# AdelinoR1.net
KiCad netlist of a schematic drawn in EAGLE
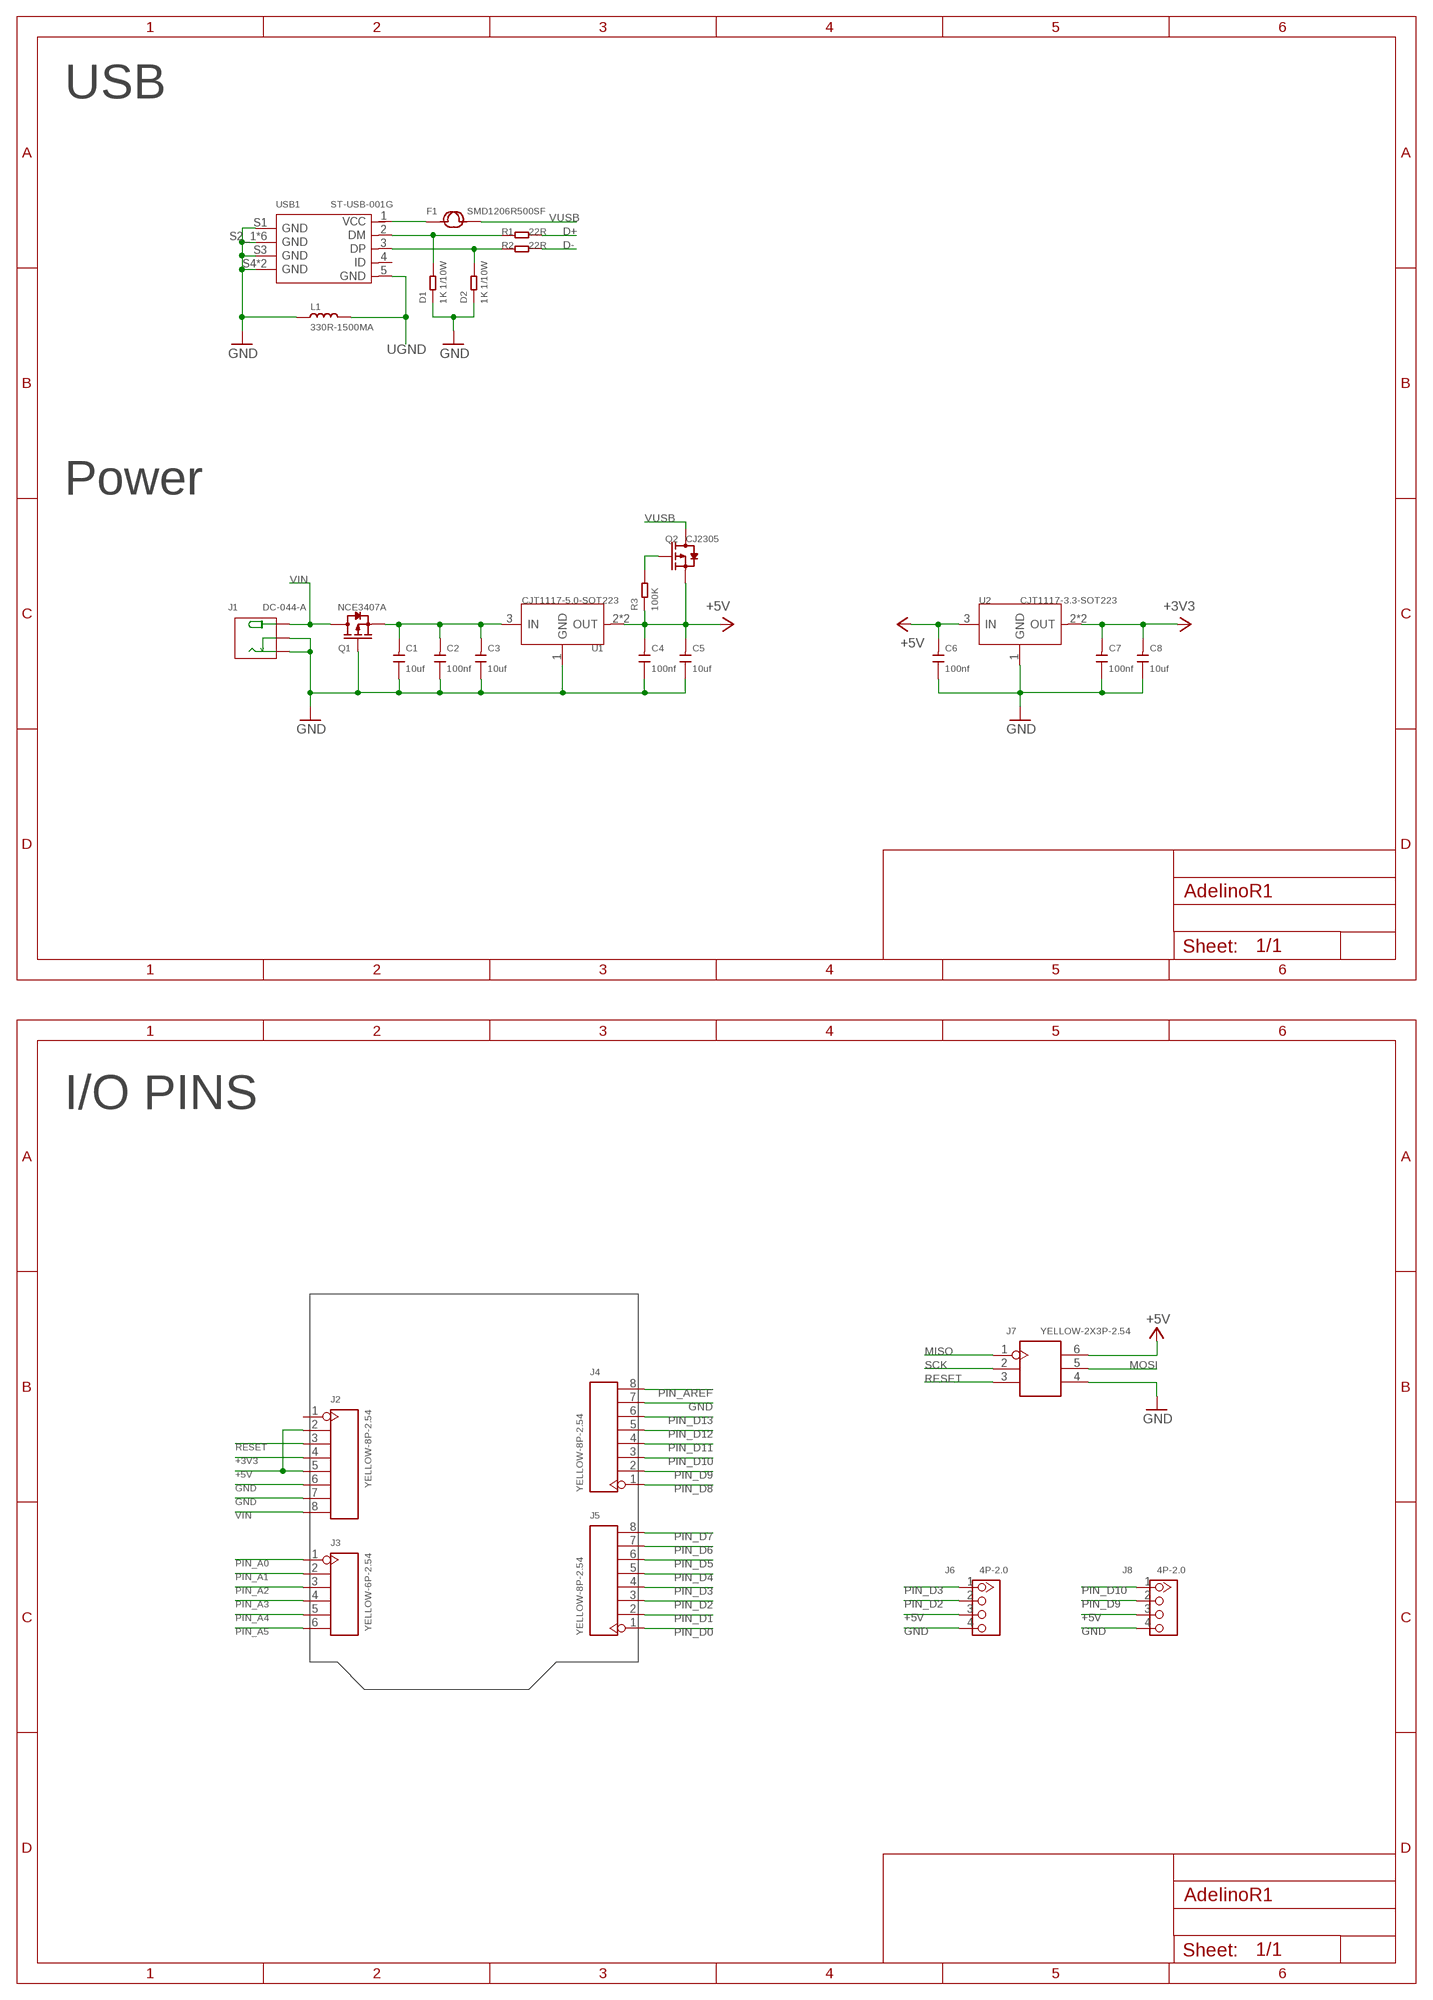
[diagram p0: schematic, sheet 1, part 1 of 2]
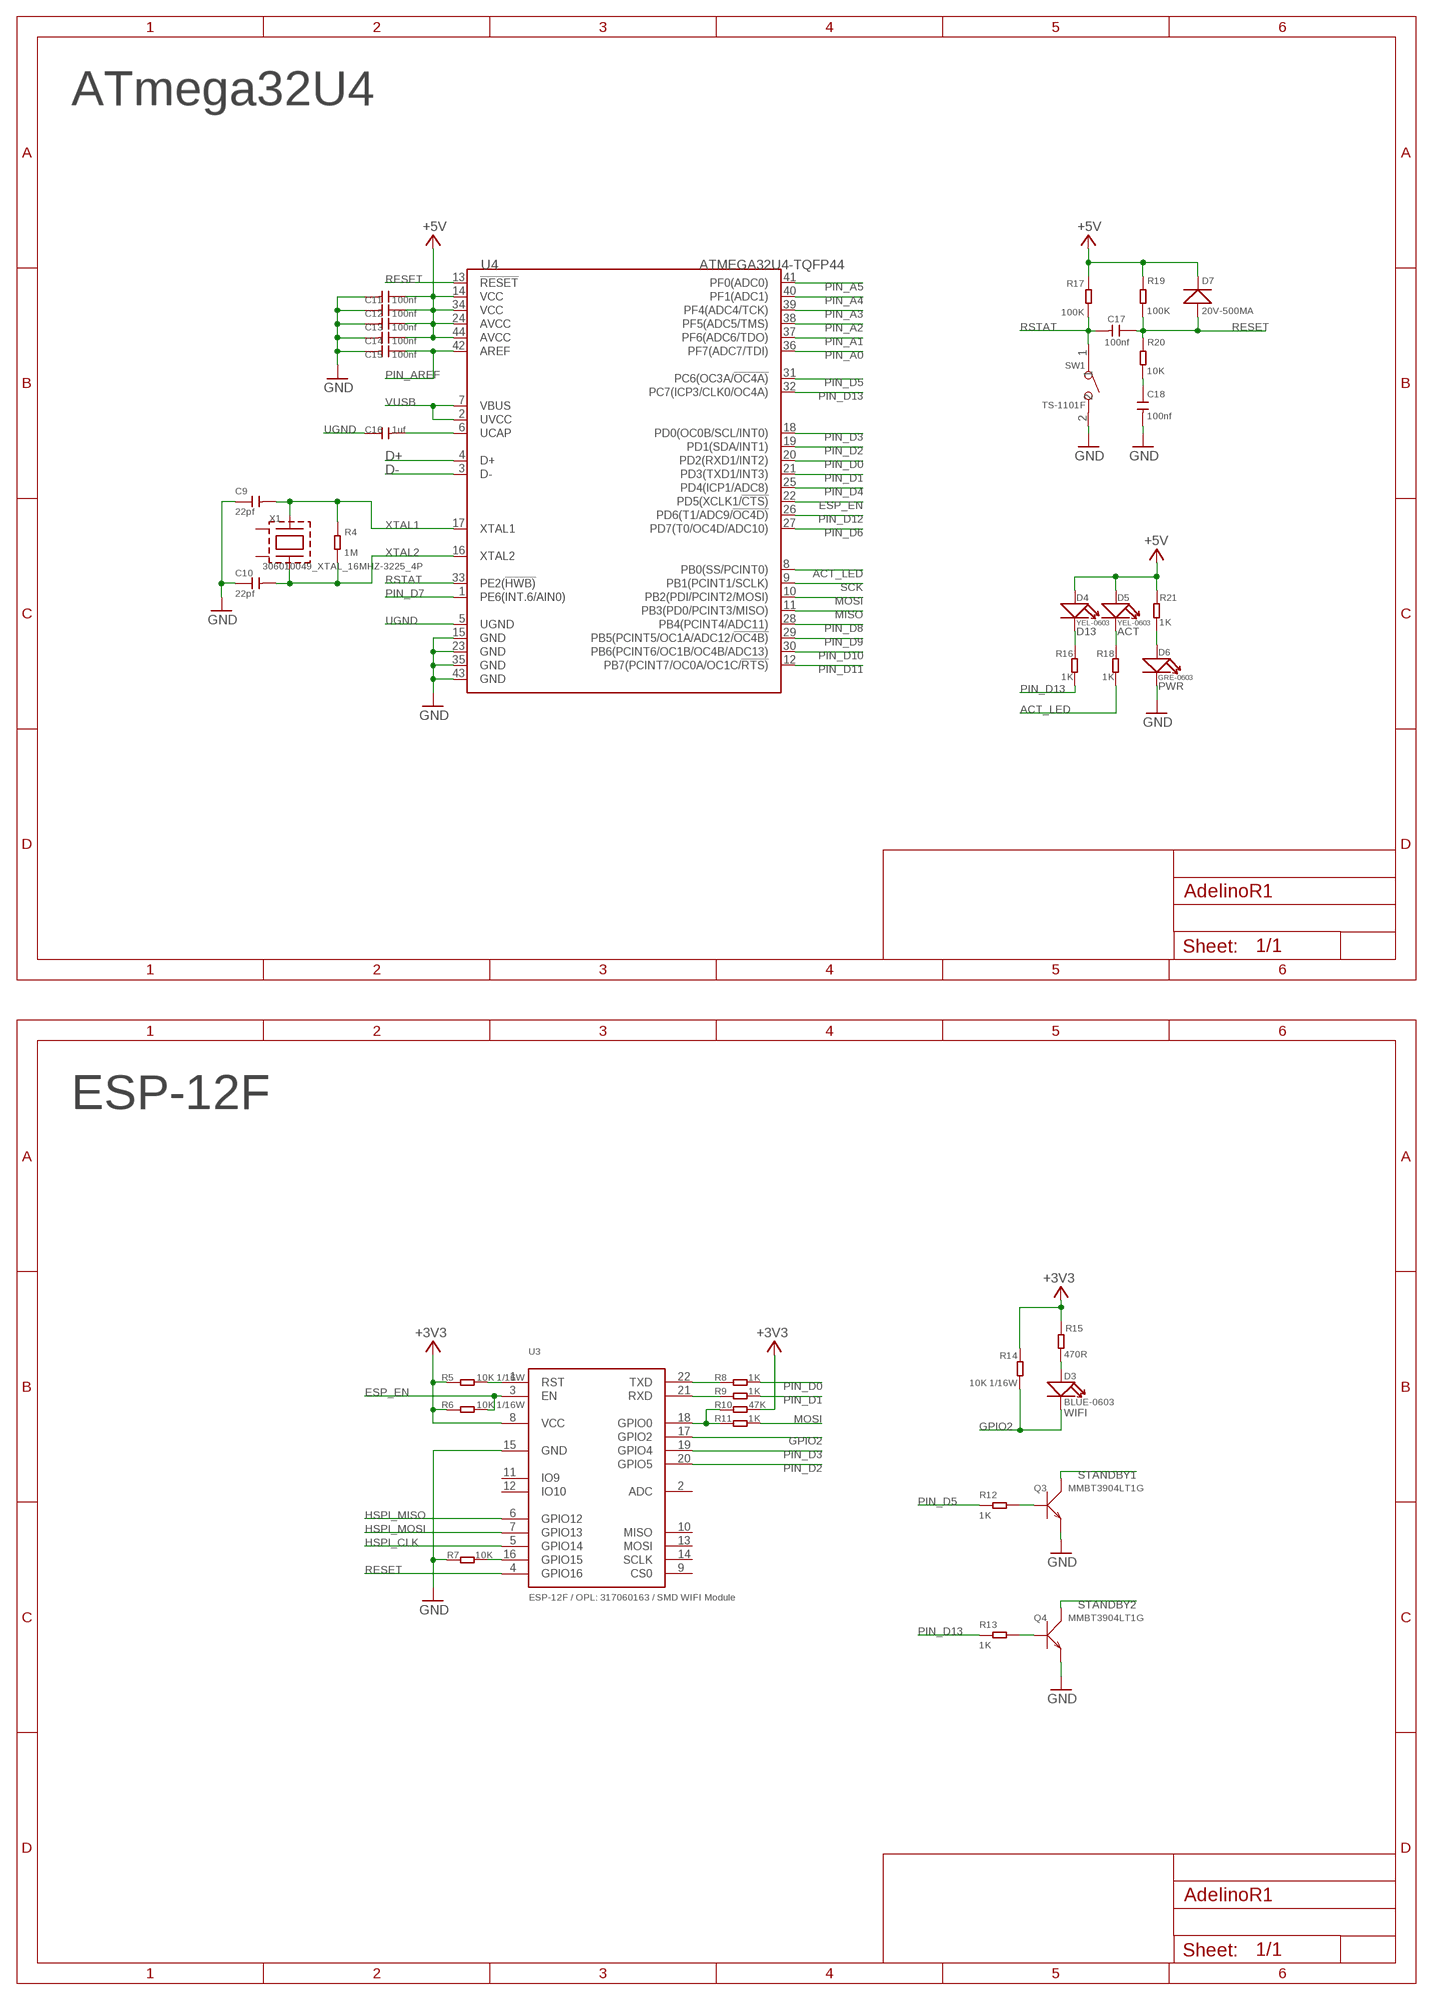
[diagram p1: schematic, sheet 1, part 2 of 2]

(export (version "E")
  (design (tool "Eeschema 10.0.6"))
  (components
    (comp (ref "C1")
      (value "10uf")
      (footprint "eagle-import:C0805")
      (fields (field (name "MPN") "CC0805KKX5R8BB106"))
      (libsource (lib "eagle-import") (part "CERAMIC-10UF-25V-10%-X5R(0805)"))
    )
    (comp (ref "C2")
      (value "100nf")
      (footprint "eagle-import:C0402")
      (fields (field (name "MPN") "CC0402KRX7R8BB104"))
      (libsource (lib "eagle-import") (part "CERAMIC-100NF-25V-10%-X7R(0402)"))
    )
    (comp (ref "C3")
      (value "10uf")
      (footprint "eagle-import:C0805")
      (fields (field (name "MPN") "CC0805KKX5R8BB106"))
      (libsource (lib "eagle-import") (part "CERAMIC-10UF-25V-10%-X5R(0805)"))
    )
    (comp (ref "C4")
      (value "100nf")
      (footprint "eagle-import:C0402")
      (fields (field (name "MPN") "CC0402KRX7R8BB104"))
      (libsource (lib "eagle-import") (part "CERAMIC-100NF-25V-10%-X7R(0402)"))
    )
    (comp (ref "C5")
      (value "10uf")
      (footprint "eagle-import:C0805")
      (fields (field (name "MPN") "CC0805KKX5R8BB106"))
      (libsource (lib "eagle-import") (part "CERAMIC-10UF-25V-10%-X5R(0805)"))
    )
    (comp (ref "C6")
      (value "100nf")
      (footprint "eagle-import:C0402")
      (fields (field (name "MPN") "CC0402KRX7R8BB104"))
      (libsource (lib "eagle-import") (part "CERAMIC-100NF-25V-10%-X7R(0402)"))
    )
    (comp (ref "C7")
      (value "100nf")
      (footprint "eagle-import:C0402")
      (fields (field (name "MPN") "CC0402KRX7R8BB104"))
      (libsource (lib "eagle-import") (part "CERAMIC-100NF-25V-10%-X7R(0402)"))
    )
    (comp (ref "C8")
      (value "10uf")
      (footprint "eagle-import:C0805")
      (fields (field (name "MPN") "CC0805KKX5R8BB106"))
      (libsource (lib "eagle-import") (part "CERAMIC-10UF-25V-10%-X5R(0805)"))
    )
    (comp (ref "C9")
      (value "22pf")
      (footprint "eagle-import:C0402")
      (fields (field (name "MPN") "CC0402JRNPO9BN220"))
      (libsource (lib "eagle-import") (part "CERAMIC-22PF-50V-5%-NPO(0402)"))
    )
    (comp (ref "C10")
      (value "22pf")
      (footprint "eagle-import:C0402")
      (fields (field (name "MPN") "CC0402JRNPO9BN220"))
      (libsource (lib "eagle-import") (part "CERAMIC-22PF-50V-5%-NPO(0402)"))
    )
    (comp (ref "C11")
      (value "100nf")
      (footprint "eagle-import:C0402")
      (fields (field (name "MPN") "CC0402KRX7R8BB104"))
      (libsource (lib "eagle-import") (part "CERAMIC-100NF-25V-10%-X7R(0402)"))
    )
    (comp (ref "C12")
      (value "100nf")
      (footprint "eagle-import:C0402")
      (fields (field (name "MPN") "CC0402KRX7R8BB104"))
      (libsource (lib "eagle-import") (part "CERAMIC-100NF-25V-10%-X7R(0402)"))
    )
    (comp (ref "C13")
      (value "100nf")
      (footprint "eagle-import:C0402")
      (fields (field (name "MPN") "CC0402KRX7R8BB104"))
      (libsource (lib "eagle-import") (part "CERAMIC-100NF-25V-10%-X7R(0402)"))
    )
    (comp (ref "C14")
      (value "100nf")
      (footprint "eagle-import:C0402")
      (fields (field (name "MPN") "CC0402KRX7R8BB104"))
      (libsource (lib "eagle-import") (part "CERAMIC-100NF-25V-10%-X7R(0402)"))
    )
    (comp (ref "C15")
      (value "100nf")
      (footprint "eagle-import:C0402")
      (fields (field (name "MPN") "CC0402KRX7R8BB104"))
      (libsource (lib "eagle-import") (part "CERAMIC-100NF-25V-10%-X7R(0402)"))
    )
    (comp (ref "C16")
      (value "1uf")
      (footprint "eagle-import:C0805")
      (fields (field (name "MPN") "CC0805KKX7R8BB105"))
      (libsource (lib "eagle-import") (part "CERAMIC-1UF-25V-10%-X7R(0805)"))
    )
    (comp (ref "C17")
      (value "100nf")
      (footprint "eagle-import:C0402")
      (fields (field (name "MPN") "CC0402KRX7R8BB104"))
      (libsource (lib "eagle-import") (part "CERAMIC-100NF-25V-10%-X7R(0402)"))
    )
    (comp (ref "C18")
      (value "100nf")
      (footprint "eagle-import:C0402")
      (fields (field (name "MPN") "CC0402KRX7R8BB104"))
      (libsource (lib "eagle-import") (part "CERAMIC-100NF-25V-10%-X7R(0402)"))
    )
    (comp (ref "D1")
      (value "1K 1/10W")
      (footprint "eagle-import:D0603")
      (fields (field (name "MPN") "RC0603JR-071KL"))
      (libsource (lib "eagle-import") (part "SMD-ESD-CG0603MLC-05E"))
    )
    (comp (ref "D2")
      (value "1K 1/10W")
      (footprint "eagle-import:D0603")
      (fields (field (name "MPN") "RC0603JR-071KL"))
      (libsource (lib "eagle-import") (part "SMD-ESD-CG0603MLC-05E"))
    )
    (comp (ref "D3")
      (value "BLUE-0603")
      (footprint "eagle-import:LED-0603")
      (fields (field (name "MPN") "19-217-BHC-ZL1M2RY-3T") (field (name "LABEL") "WIFI"))
      (libsource (lib "eagle-import") (part "SMD-LED-CLEAR-BLUE(0603)"))
    )
    (comp (ref "D4")
      (value "YEL-0603")
      (footprint "eagle-import:LED-0603")
      (fields (field (name "MPN") "19-217-Y5C-AM1N1VY-3T") (field (name "LABEL") "D13"))
      (libsource (lib "eagle-import") (part "SMD-LED-CLEAR-YELLOW(0603)"))
    )
    (comp (ref "D5")
      (value "YEL-0603")
      (footprint "eagle-import:LED-0603")
      (fields (field (name "MPN") "19-217-Y5C-AM1N1VY-3T") (field (name "LABEL") "ACT"))
      (libsource (lib "eagle-import") (part "SMD-LED-CLEAR-YELLOW(0603)"))
    )
    (comp (ref "D6")
      (value "GRE-0603")
      (footprint "eagle-import:LED-0603")
      (fields (field (name "MPN") "19-217-G7C-AN1P2-3T") (field (name "LABEL") "PWR"))
      (libsource (lib "eagle-import") (part "SMD-LED-CLEAR-GREEN(0603)"))
    )
    (comp (ref "D7")
      (value "20V-500MA")
      (footprint "eagle-import:SOD-123")
      (fields (field (name "MPN") "MBR0520LT1G"))
      (libsource (lib "eagle-import") (part "SMD-DIODE-SCHOTTKY-20V-500MA(SOD-123)P"))
    )
    (comp (ref "F1")
      (value "SMD1206R500SF")
      (footprint "eagle-import:F1206")
      (libsource (lib "eagle-import") (part "SMD-PPTC-500MA(1206)"))
    )
    (comp (ref "J1")
      (value "DC-044-A")
      (footprint "eagle-import:DCJ3P-11.6X9.6X7.0MM")
      (fields (field (name "MPN") "JACK-DC-044-A"))
      (libsource (lib "eagle-import") (part "JACK-DC-044-A"))
    )
    (comp (ref "J2")
      (value "YELLOW-8P-2.54")
      (footprint "eagle-import:H8-2.54")
      (fields (field (name "MPN") "F185-1108A1BSYC1"))
      (libsource (lib "eagle-import") (part "DIP-YELLOW-FEMALE-HEADER(8P-2.54)"))
    )
    (comp (ref "J3")
      (value "YELLOW-6P-2.54")
      (footprint "eagle-import:H6-2.54")
      (fields (field (name "MPN") "F185-1106A1BSYA3"))
      (libsource (lib "eagle-import") (part "DIP-YELLOW-FEMALE-HEADER-VERT(6P-2.54)"))
    )
    (comp (ref "J4")
      (value "YELLOW-8P-2.54")
      (footprint "eagle-import:H8-2.54")
      (fields (field (name "MPN") "F185-1108A1BSYC1"))
      (libsource (lib "eagle-import") (part "DIP-YELLOW-FEMALE-HEADER(8P-2.54)"))
    )
    (comp (ref "J5")
      (value "YELLOW-8P-2.54")
      (footprint "eagle-import:H8-2.54")
      (fields (field (name "MPN") "F185-1108A1BSYC1"))
      (libsource (lib "eagle-import") (part "DIP-YELLOW-FEMALE-HEADER(8P-2.54)"))
    )
    (comp (ref "J6")
      (value "4P-2.0")
      (footprint "eagle-import:HW4-2.0")
      (libsource (lib "eagle-import") (part "GROVE-CONNECTOR-DIP(4P-2.0)"))
    )
    (comp (ref "J7")
      (value "YELLOW-2X3P-2.54")
      (footprint "eagle-import:H2X3-2.54")
      (fields (field (name "MPN") "P125-1203A0BS116A2"))
      (libsource (lib "eagle-import") (part "DIP-YELLOW-MALE-HEADER-VERT(2X3P-2.54)"))
    )
    (comp (ref "J8")
      (value "4P-2.0")
      (footprint "eagle-import:HW4-2.0")
      (libsource (lib "eagle-import") (part "GROVE-CONNECTOR-DIP(4P-2.0)"))
    )
    (comp (ref "L1")
      (value "330R-1500MA")
      (footprint "eagle-import:L0805")
      (fields (field (name "MPN") "BLM21PG331SN1D"))
      (libsource (lib "eagle-import") (part "SMD-FERRITE-BEAD-330R-1500MA(0805)'0805'"))
    )
    (comp (ref "Q1")
      (value "NCE3407A")
      (footprint "eagle-import:SOT-23")
      (libsource (lib "eagle-import") (part "SMD-MOSFET-P-CH-VDC=30V-ID=4.3A-NCE3407A(SOT-23)"))
    )
    (comp (ref "Q2")
      (value "CJ2305")
      (footprint "eagle-import:SOT-23")
      (libsource (lib "eagle-import") (part "SMD-MOSFET-P-CH-8V-4.1A-CJ2305(SOT-23)"))
    )
    (comp (ref "Q3")
      (value "MMBT3904LT1G")
      (footprint "eagle-import:SOT-23")
      (libsource (lib "eagle-import") (part "SMD-TRANSISTORS-NPN-40V-200MA-MMBT3904LT1G(SOT-23)"))
    )
    (comp (ref "Q4")
      (value "MMBT3904LT1G")
      (footprint "eagle-import:SOT-23")
      (libsource (lib "eagle-import") (part "SMD-TRANSISTORS-NPN-40V-200MA-MMBT3904LT1G(SOT-23)"))
    )
    (comp (ref "R1")
      (value "22R")
      (footprint "eagle-import:R0402")
      (fields (field (name "MPN") "RC0402FR-0722RL"))
      (libsource (lib "eagle-import") (part "SMD-RES-22R-1%-1/16W(0402)"))
    )
    (comp (ref "R2")
      (value "22R")
      (footprint "eagle-import:R0402")
      (fields (field (name "MPN") "RC0402FR-0722RL"))
      (libsource (lib "eagle-import") (part "SMD-RES-22R-1%-1/16W(0402)"))
    )
    (comp (ref "R3")
      (value "100K")
      (footprint "eagle-import:R0402")
      (fields (field (name "MPN") "RC0402FR-07100KL"))
      (libsource (lib "eagle-import") (part "SMD-RES-100K-1%-1/16W(0402)"))
    )
    (comp (ref "R4")
      (value "1M")
      (footprint "eagle-import:R0402")
      (fields (field (name "MPN") "RC0402FR-071ML"))
      (libsource (lib "eagle-import") (part "SMD-RES-1M-1%-1/16W(0402)"))
    )
    (comp (ref "R5")
      (value "10K 1/16W")
      (footprint "eagle-import:R0402")
      (fields (field (name "MPN") "RC0402FR-0710KL"))
      (libsource (lib "eagle-import") (part "SMD-RES-10K-1%-1/16W(0402)"))
    )
    (comp (ref "R6")
      (value "10K 1/16W")
      (footprint "eagle-import:R0402")
      (fields (field (name "MPN") "RC0402FR-0710KL"))
      (libsource (lib "eagle-import") (part "SMD-RES-10K-1%-1/16W(0402)"))
    )
    (comp (ref "R7")
      (value "10K")
      (footprint "eagle-import:R0402")
      (fields (field (name "MPN") "RC0402FR-0710KL"))
      (libsource (lib "eagle-import") (part "SMD-RES-10K-1%-1/16W(0402)"))
    )
    (comp (ref "R8")
      (value "1K")
      (footprint "eagle-import:R0402")
      (fields (field (name "MPN") "RC0402JR-071KL"))
      (libsource (lib "eagle-import") (part "SMD-RES-1K-5%-1/16W(0402)"))
    )
    (comp (ref "R9")
      (value "1K")
      (footprint "eagle-import:R0402")
      (fields (field (name "MPN") "RC0402JR-071KL"))
      (libsource (lib "eagle-import") (part "SMD-RES-1K-5%-1/16W(0402)"))
    )
    (comp (ref "R10")
      (value "47K")
      (footprint "eagle-import:R0402")
      (fields (field (name "MPN") "RC0402JR-0747KL"))
      (libsource (lib "eagle-import") (part "SMD-RES-47K-5%-1/16W(0402)"))
    )
    (comp (ref "R11")
      (value "1K")
      (footprint "eagle-import:R0402")
      (fields (field (name "MPN") "RC0402JR-071KL"))
      (libsource (lib "eagle-import") (part "SMD-RES-1K-5%-1/16W(0402)"))
    )
    (comp (ref "R12")
      (value "1K")
      (footprint "eagle-import:R0402")
      (fields (field (name "MPN") "RC0402JR-071KL"))
      (libsource (lib "eagle-import") (part "SMD-RES-1K-5%-1/16W(0402)"))
    )
    (comp (ref "R13")
      (value "1K")
      (footprint "eagle-import:R0402")
      (fields (field (name "MPN") "RC0402JR-071KL"))
      (libsource (lib "eagle-import") (part "SMD-RES-1K-5%-1/16W(0402)"))
    )
    (comp (ref "R14")
      (value "10K 1/16W")
      (footprint "eagle-import:R0402")
      (fields (field (name "MPN") "RC0402FR-0710KL"))
      (libsource (lib "eagle-import") (part "SMD-RES-10K-1%-1/16W(0402)"))
    )
    (comp (ref "R15")
      (value "470R")
      (footprint "eagle-import:R0402")
      (fields (field (name "MPN") "RC0402JR-07470RL"))
      (libsource (lib "eagle-import") (part "SMD-RES-470R-5%-1/16W(0402)"))
    )
    (comp (ref "R16")
      (value "1K")
      (footprint "eagle-import:R0402")
      (fields (field (name "MPN") "RC0402JR-071KL"))
      (libsource (lib "eagle-import") (part "SMD-RES-1K-5%-1/16W(0402)"))
    )
    (comp (ref "R17")
      (value "100K")
      (footprint "eagle-import:R0402")
      (fields (field (name "MPN") "RC0402FR-07100KL"))
      (libsource (lib "eagle-import") (part "SMD-RES-100K-1%-1/16W(0402)"))
    )
    (comp (ref "R18")
      (value "1K")
      (footprint "eagle-import:R0402")
      (fields (field (name "MPN") "RC0402JR-071KL"))
      (libsource (lib "eagle-import") (part "SMD-RES-1K-5%-1/16W(0402)"))
    )
    (comp (ref "R19")
      (value "100K")
      (footprint "eagle-import:R0402")
      (fields (field (name "MPN") "RC0402FR-07100KL"))
      (libsource (lib "eagle-import") (part "SMD-RES-100K-1%-1/16W(0402)"))
    )
    (comp (ref "R20")
      (value "10K")
      (footprint "eagle-import:R0402")
      (fields (field (name "MPN") "RC0402FR-0710KL"))
      (libsource (lib "eagle-import") (part "SMD-RES-10K-1%-1/16W(0402)"))
    )
    (comp (ref "R21")
      (value "1K")
      (footprint "eagle-import:R0402")
      (fields (field (name "MPN") "RC0402JR-071KL"))
      (libsource (lib "eagle-import") (part "SMD-RES-1K-5%-1/16W(0402)"))
    )
    (comp (ref "SW1")
      (value "TS-1101F")
      (footprint "eagle-import:SW2-5.0-6.0X3.0X4.3MM")
      (libsource (lib "eagle-import") (part "DIP-BUTTON(2P-6.0X3.0X4.3MM)-TS-1101F"))
    )
    (comp (ref "U1")
      (value "CJT1117-5.0-SOT223")
      (footprint "eagle-import:SOT-223")
      (fields (field (name "MPN") "CJT1117-5.0"))
      (libsource (lib "eagle-import") (part "PMIC-CJT1117-5.0(SOT223)"))
    )
    (comp (ref "U2")
      (value "CJT1117-3.3-SOT223")
      (footprint "eagle-import:SOT-223")
      (fields (field (name "MPN") "CJT1117-3.3"))
      (libsource (lib "eagle-import") (part "PMIC-CJT1117-3.3(SOT223)"))
    )
    (comp (ref "U3")
      (value "ESP-12F / OPL: 317060163 / SMD WIFI Module")
      (footprint "eagle-import:ESP-12F")
      (libsource (lib "eagle-import") (part "ESP-12F"))
    )
    (comp (ref "U4")
      (value "ATMEGA32U4-TQFP44")
      (footprint "eagle-import:TQFP44-0.8-9.6X9.6MM")
      (fields (field (name "MPN") "ATMEGA32U4"))
      (libsource (lib "eagle-import") (part "MCU-ATMEGA32U4-AU(TQFP44)"))
    )
    (comp (ref "USB1")
      (value "ST-USB-001G")
      (footprint "eagle-import:MICRO-USB5+4P-SMD-0.65-B")
      (libsource (lib "eagle-import") (part "MICRO-USB-SMD-B-WITHOUT-POST-W/P(ST-USB-001G)"))
    )
    (comp (ref "X1")
      (value "306010049_XTAL_16MHZ-3225_4P")
      (footprint "eagle-import:X3225_4P")
      (libsource (lib "eagle-import") (part "306010049_XTAL_16MHZ-3225_4P"))
    )
  )
  (nets
    (net (code "1") (name "+3V3") (class "Default")
      (node (ref "C7") (pin "2") (pinfunction "2_2") (pintype "passive"))
      (node (ref "C8") (pin "2") (pinfunction "2_2") (pintype "passive"))
      (node (ref "J2") (pin "4") (pinfunction "4_4") (pintype "bidirectional"))
      (node (ref "R10") (pin "2") (pinfunction "2_2") (pintype "passive"))
      (node (ref "R14") (pin "2") (pinfunction "2_2") (pintype "passive"))
      (node (ref "R15") (pin "2") (pinfunction "2_2") (pintype "passive"))
      (node (ref "R5") (pin "1") (pinfunction "1_1") (pintype "passive"))
      (node (ref "R6") (pin "1") (pinfunction "1_1") (pintype "passive"))
      (node (ref "U2") (pin "2") (pinfunction "OUT_2") (pintype "bidirectional"))
      (node (ref "U2") (pin "TER") (pinfunction "OUT_TER") (pintype "bidirectional"))
      (node (ref "U3") (pin "8") (pinfunction "VCC_8") (pintype "bidirectional"))
    )
    (net (code "2") (name "+5V") (class "Default")
      (node (ref "C11") (pin "1") (pinfunction "1_1") (pintype "passive"))
      (node (ref "C12") (pin "1") (pinfunction "1_1") (pintype "passive"))
      (node (ref "C13") (pin "1") (pinfunction "1_1") (pintype "passive"))
      (node (ref "C14") (pin "1") (pinfunction "1_1") (pintype "passive"))
      (node (ref "C4") (pin "2") (pinfunction "2_2") (pintype "passive"))
      (node (ref "C5") (pin "2") (pinfunction "2_2") (pintype "passive"))
      (node (ref "C6") (pin "2") (pinfunction "2_2") (pintype "passive"))
      (node (ref "D4") (pin "+") (pinfunction "+_+") (pintype "passive"))
      (node (ref "D5") (pin "+") (pinfunction "+_+") (pintype "passive"))
      (node (ref "D7") (pin "-") (pinfunction "-_-") (pintype "passive"))
      (node (ref "J2") (pin "2") (pinfunction "2_2") (pintype "bidirectional"))
      (node (ref "J2") (pin "5") (pinfunction "5_5") (pintype "bidirectional"))
      (node (ref "J6") (pin "3") (pinfunction "3_3") (pintype "bidirectional"))
      (node (ref "J7") (pin "6") (pinfunction "6_6") (pintype "bidirectional"))
      (node (ref "J8") (pin "3") (pinfunction "3_3") (pintype "bidirectional"))
      (node (ref "Q2") (pin "2") (pinfunction "S_2") (pintype "passive"))
      (node (ref "R17") (pin "1") (pinfunction "1_1") (pintype "passive"))
      (node (ref "R19") (pin "2") (pinfunction "2_2") (pintype "passive"))
      (node (ref "R21") (pin "1") (pinfunction "1_1") (pintype "passive"))
      (node (ref "R3") (pin "1") (pinfunction "1_1") (pintype "passive"))
      (node (ref "U1") (pin "2") (pinfunction "OUT_2") (pintype "bidirectional"))
      (node (ref "U1") (pin "TER") (pinfunction "OUT_TER") (pintype "bidirectional"))
      (node (ref "U2") (pin "3") (pinfunction "IN_3") (pintype "bidirectional"))
      (node (ref "U4") (pin "14") (pinfunction "VCC_14") (pintype "bidirectional"))
      (node (ref "U4") (pin "24") (pinfunction "AVCC_24") (pintype "bidirectional"))
      (node (ref "U4") (pin "34") (pinfunction "VCC_34") (pintype "bidirectional"))
      (node (ref "U4") (pin "44") (pinfunction "AVCC_44") (pintype "bidirectional"))
    )
    (net (code "3") (name "/ACT_LED") (class "Default")
      (node (ref "R18") (pin "2") (pinfunction "2_2") (pintype "passive"))
      (node (ref "U4") (pin "8") (pinfunction "PB0(SS/PCINT0)_8") (pintype "bidirectional"))
    )
    (net (code "4") (name "/D+") (class "Default")
      (node (ref "R1") (pin "2") (pinfunction "2_2") (pintype "passive"))
      (node (ref "U4") (pin "4") (pinfunction "D+_4") (pintype "bidirectional"))
    )
    (net (code "5") (name "/D-") (class "Default")
      (node (ref "R2") (pin "2") (pinfunction "2_2") (pintype "passive"))
      (node (ref "U4") (pin "3") (pinfunction "D-_3") (pintype "bidirectional"))
    )
    (net (code "6") (name "/ESP_EN") (class "Default")
      (node (ref "R6") (pin "2") (pinfunction "2_2") (pintype "passive"))
      (node (ref "U3") (pin "3") (pinfunction "EN_3") (pintype "bidirectional"))
      (node (ref "U4") (pin "22") (pinfunction "PD5(XCLK1/~{CTS})_22") (pintype "bidirectional"))
    )
    (net (code "7") (name "/GND1") (class "Default")
      (node (ref "X1") (pin "P$2") (pinfunction "GND1_P$2") (pintype "power_in"))
    )
    (net (code "8") (name "/GND2") (class "Default")
      (node (ref "X1") (pin "P$4") (pinfunction "GND2_P$4") (pintype "power_in"))
    )
    (net (code "9") (name "/GPIO2") (class "Default")
      (node (ref "D3") (pin "-") (pinfunction "-_-") (pintype "passive"))
      (node (ref "R14") (pin "1") (pinfunction "1_1") (pintype "passive"))
      (node (ref "U3") (pin "17") (pinfunction "GPIO2_17") (pintype "bidirectional"))
    )
    (net (code "10") (name "/HSPI_CLK") (class "Default")
      (node (ref "U3") (pin "5") (pinfunction "GPIO14_5") (pintype "bidirectional"))
    )
    (net (code "11") (name "/HSPI_MISO") (class "Default")
      (node (ref "U3") (pin "6") (pinfunction "GPIO12_6") (pintype "bidirectional"))
    )
    (net (code "12") (name "/HSPI_MOSI") (class "Default")
      (node (ref "U3") (pin "7") (pinfunction "GPIO13_7") (pintype "bidirectional"))
    )
    (net (code "13") (name "/MISO") (class "Default")
      (node (ref "J7") (pin "1") (pinfunction "1_1") (pintype "bidirectional"))
      (node (ref "U4") (pin "11") (pinfunction "PB3(PD0/PCINT3/MISO)_11") (pintype "bidirectional"))
    )
    (net (code "14") (name "/MOSI") (class "Default")
      (node (ref "J7") (pin "5") (pinfunction "5_5") (pintype "bidirectional"))
      (node (ref "R11") (pin "2") (pinfunction "2_2") (pintype "passive"))
      (node (ref "U4") (pin "10") (pinfunction "PB2(PDI/PCINT2/MOSI)_10") (pintype "bidirectional"))
    )
    (net (code "15") (name "/PIN_A0") (class "Default")
      (node (ref "J3") (pin "1") (pinfunction "1_1") (pintype "bidirectional"))
      (node (ref "U4") (pin "36") (pinfunction "PF7(ADC7/TDI)_36") (pintype "bidirectional"))
    )
    (net (code "16") (name "/PIN_A1") (class "Default")
      (node (ref "J3") (pin "2") (pinfunction "2_2") (pintype "bidirectional"))
      (node (ref "U4") (pin "37") (pinfunction "PF6(ADC6/TDO)_37") (pintype "bidirectional"))
    )
    (net (code "17") (name "/PIN_A2") (class "Default")
      (node (ref "J3") (pin "3") (pinfunction "3_3") (pintype "bidirectional"))
      (node (ref "U4") (pin "38") (pinfunction "PF5(ADC5/TMS)_38") (pintype "bidirectional"))
    )
    (net (code "18") (name "/PIN_A3") (class "Default")
      (node (ref "J3") (pin "4") (pinfunction "4_4") (pintype "bidirectional"))
      (node (ref "U4") (pin "39") (pinfunction "PF4(ADC4/TCK)_39") (pintype "bidirectional"))
    )
    (net (code "19") (name "/PIN_A4") (class "Default")
      (node (ref "J3") (pin "5") (pinfunction "5_5") (pintype "bidirectional"))
      (node (ref "U4") (pin "40") (pinfunction "PF1(ADC1)_40") (pintype "bidirectional"))
    )
    (net (code "20") (name "/PIN_A5") (class "Default")
      (node (ref "J3") (pin "6") (pinfunction "6_6") (pintype "bidirectional"))
      (node (ref "U4") (pin "41") (pinfunction "PF0(ADC0)_41") (pintype "bidirectional"))
    )
    (net (code "21") (name "/PIN_AREF") (class "Default")
      (node (ref "C15") (pin "1") (pinfunction "1_1") (pintype "passive"))
      (node (ref "J4") (pin "8") (pinfunction "8_8") (pintype "bidirectional"))
      (node (ref "U4") (pin "42") (pinfunction "AREF_42") (pintype "bidirectional"))
    )
    (net (code "22") (name "/PIN_D0") (class "Default")
      (node (ref "J5") (pin "1") (pinfunction "1_1") (pintype "bidirectional"))
      (node (ref "R8") (pin "2") (pinfunction "2_2") (pintype "passive"))
      (node (ref "U4") (pin "20") (pinfunction "PD2(RXD1/INT2)_20") (pintype "bidirectional"))
    )
    (net (code "23") (name "/PIN_D1") (class "Default")
      (node (ref "J5") (pin "2") (pinfunction "2_2") (pintype "bidirectional"))
      (node (ref "R9") (pin "2") (pinfunction "2_2") (pintype "passive"))
      (node (ref "U4") (pin "21") (pinfunction "PD3(TXD1/INT3)_21") (pintype "bidirectional"))
    )
    (net (code "24") (name "/PIN_D2") (class "Default")
      (node (ref "J5") (pin "3") (pinfunction "3_3") (pintype "bidirectional"))
      (node (ref "J6") (pin "2") (pinfunction "2_2") (pintype "bidirectional"))
      (node (ref "U3") (pin "20") (pinfunction "GPIO5_20") (pintype "bidirectional"))
      (node (ref "U4") (pin "19") (pinfunction "PD1(SDA/INT1)_19") (pintype "bidirectional"))
    )
    (net (code "25") (name "/PIN_D3") (class "Default")
      (node (ref "J5") (pin "4") (pinfunction "4_4") (pintype "bidirectional"))
      (node (ref "J6") (pin "1") (pinfunction "1_1") (pintype "bidirectional"))
      (node (ref "U3") (pin "19") (pinfunction "GPIO4_19") (pintype "bidirectional"))
      (node (ref "U4") (pin "18") (pinfunction "PD0(OC0B/SCL/INT0)_18") (pintype "bidirectional"))
    )
    (net (code "26") (name "/PIN_D4") (class "Default")
      (node (ref "J5") (pin "5") (pinfunction "5_5") (pintype "bidirectional"))
      (node (ref "U4") (pin "25") (pinfunction "PD4(ICP1/ADC8)_25") (pintype "bidirectional"))
    )
    (net (code "27") (name "/PIN_D5") (class "Default")
      (node (ref "J5") (pin "6") (pinfunction "6_6") (pintype "bidirectional"))
      (node (ref "R12") (pin "1") (pinfunction "1_1") (pintype "passive"))
      (node (ref "U4") (pin "31") (pinfunction "PC6(OC3A/~{OC4A})_31") (pintype "bidirectional"))
    )
    (net (code "28") (name "/PIN_D6") (class "Default")
      (node (ref "J5") (pin "7") (pinfunction "7_7") (pintype "bidirectional"))
      (node (ref "U4") (pin "27") (pinfunction "PD7(T0/OC4D/ADC10)_27") (pintype "bidirectional"))
    )
    (net (code "29") (name "/PIN_D7") (class "Default")
      (node (ref "J5") (pin "8") (pinfunction "8_8") (pintype "bidirectional"))
      (node (ref "U4") (pin "1") (pinfunction "PE6(INT.6/AIN0)_1") (pintype "bidirectional"))
    )
    (net (code "30") (name "/PIN_D8") (class "Default")
      (node (ref "J4") (pin "1") (pinfunction "1_1") (pintype "bidirectional"))
      (node (ref "U4") (pin "28") (pinfunction "PB4(PCINT4/ADC11)_28") (pintype "bidirectional"))
    )
    (net (code "31") (name "/PIN_D9") (class "Default")
      (node (ref "J4") (pin "2") (pinfunction "2_2") (pintype "bidirectional"))
      (node (ref "J8") (pin "2") (pinfunction "2_2") (pintype "bidirectional"))
      (node (ref "U4") (pin "29") (pinfunction "PB5(PCINT5/OC1A/ADC12/~{OC4B})_29") (pintype "bidirectional"))
    )
    (net (code "32") (name "/PIN_D10") (class "Default")
      (node (ref "J4") (pin "3") (pinfunction "3_3") (pintype "bidirectional"))
      (node (ref "J8") (pin "1") (pinfunction "1_1") (pintype "bidirectional"))
      (node (ref "U4") (pin "30") (pinfunction "PB6(PCINT6/OC1B/OC4B/ADC13)_30") (pintype "bidirectional"))
    )
    (net (code "33") (name "/PIN_D11") (class "Default")
      (node (ref "J4") (pin "4") (pinfunction "4_4") (pintype "bidirectional"))
      (node (ref "U4") (pin "12") (pinfunction "PB7(PCINT7/OC0A/OC1C/~{RTS})_12") (pintype "bidirectional"))
    )
    (net (code "34") (name "/PIN_D12") (class "Default")
      (node (ref "J4") (pin "5") (pinfunction "5_5") (pintype "bidirectional"))
      (node (ref "U4") (pin "26") (pinfunction "PD6(T1/ADC9/~{OC4D})_26") (pintype "bidirectional"))
    )
    (net (code "35") (name "/PIN_D13") (class "Default")
      (node (ref "J4") (pin "6") (pinfunction "6_6") (pintype "bidirectional"))
      (node (ref "R13") (pin "1") (pinfunction "1_1") (pintype "passive"))
      (node (ref "R16") (pin "2") (pinfunction "2_2") (pintype "passive"))
      (node (ref "U4") (pin "32") (pinfunction "PC7(ICP3/CLK0/OC4A)_32") (pintype "bidirectional"))
    )
    (net (code "36") (name "/RESET") (class "Default")
      (node (ref "C17") (pin "1") (pinfunction "1_1") (pintype "passive"))
      (node (ref "D7") (pin "+") (pinfunction "+_+") (pintype "passive"))
      (node (ref "J2") (pin "3") (pinfunction "3_3") (pintype "bidirectional"))
      (node (ref "J7") (pin "3") (pinfunction "3_3") (pintype "bidirectional"))
      (node (ref "R19") (pin "1") (pinfunction "1_1") (pintype "passive"))
      (node (ref "R20") (pin "1") (pinfunction "1_1") (pintype "passive"))
      (node (ref "U3") (pin "4") (pinfunction "GPIO16_4") (pintype "bidirectional"))
      (node (ref "U4") (pin "13") (pinfunction "~{RESET}_13") (pintype "bidirectional"))
    )
    (net (code "37") (name "/RSTAT") (class "Default")
      (node (ref "C17") (pin "2") (pinfunction "2_2") (pintype "passive"))
      (node (ref "R17") (pin "2") (pinfunction "2_2") (pintype "passive"))
      (node (ref "SW1") (pin "1") (pinfunction "1_1") (pintype "bidirectional"))
      (node (ref "U4") (pin "33") (pinfunction "PE2(~{HWB})_33") (pintype "bidirectional"))
    )
    (net (code "38") (name "/SCK") (class "Default")
      (node (ref "J7") (pin "2") (pinfunction "2_2") (pintype "bidirectional"))
      (node (ref "U4") (pin "9") (pinfunction "PB1(PCINT1/SCLK)_9") (pintype "bidirectional"))
    )
    (net (code "39") (name "/STANDBY1") (class "Default")
      (node (ref "Q3") (pin "3") (pinfunction "C_3") (pintype "passive"))
    )
    (net (code "40") (name "/STANDBY2") (class "Default")
      (node (ref "Q4") (pin "3") (pinfunction "C_3") (pintype "passive"))
    )
    (net (code "41") (name "/UGND") (class "Default")
      (node (ref "C16") (pin "1") (pinfunction "1_1") (pintype "passive"))
      (node (ref "L1") (pin "2") (pinfunction "2_2") (pintype "passive"))
      (node (ref "U4") (pin "5") (pinfunction "UGND_5") (pintype "bidirectional"))
      (node (ref "USB1") (pin "5") (pinfunction "GND_5") (pintype "bidirectional"))
    )
    (net (code "42") (name "/VIN") (class "Default")
      (node (ref "J1") (pin "VCC1") (pinfunction "+_VCC1") (pintype "bidirectional"))
      (node (ref "J1") (pin "VCC2") (pinfunction "+_VCC2") (pintype "bidirectional"))
      (node (ref "J1") (pin "VCC3") (pinfunction "+_VCC3") (pintype "bidirectional"))
      (node (ref "J1") (pin "VCC4") (pinfunction "+_VCC4") (pintype "bidirectional"))
      (node (ref "J2") (pin "8") (pinfunction "8_8") (pintype "bidirectional"))
      (node (ref "Q1") (pin "3") (pinfunction "D_3") (pintype "passive"))
    )
    (net (code "43") (name "/VUSB") (class "Default")
      (node (ref "F1") (pin "2") (pinfunction "2_2") (pintype "bidirectional"))
      (node (ref "Q2") (pin "3") (pinfunction "D_3") (pintype "passive"))
      (node (ref "U4") (pin "2") (pinfunction "UVCC_2") (pintype "bidirectional"))
      (node (ref "U4") (pin "7") (pinfunction "VBUS_7") (pintype "bidirectional"))
    )
    (net (code "44") (name "/XTAL1") (class "Default")
      (node (ref "C9") (pin "2") (pinfunction "2_2") (pintype "passive"))
      (node (ref "R4") (pin "2") (pinfunction "2_2") (pintype "passive"))
      (node (ref "U4") (pin "17") (pinfunction "XTAL1_17") (pintype "bidirectional"))
      (node (ref "X1") (pin "P$1") (pinfunction "P$1_P$1") (pintype "passive"))
    )
    (net (code "45") (name "/XTAL2") (class "Default")
      (node (ref "C10") (pin "2") (pinfunction "2_2") (pintype "passive"))
      (node (ref "R4") (pin "1") (pinfunction "1_1") (pintype "passive"))
      (node (ref "U4") (pin "16") (pinfunction "XTAL2_16") (pintype "bidirectional"))
      (node (ref "X1") (pin "P$3") (pinfunction "P$2_P$3") (pintype "passive"))
    )
    (net (code "46") (name "GND") (class "Default")
      (node (ref "C1") (pin "1") (pinfunction "1_1") (pintype "passive"))
      (node (ref "C10") (pin "1") (pinfunction "1_1") (pintype "passive"))
      (node (ref "C11") (pin "2") (pinfunction "2_2") (pintype "passive"))
      (node (ref "C12") (pin "2") (pinfunction "2_2") (pintype "passive"))
      (node (ref "C13") (pin "2") (pinfunction "2_2") (pintype "passive"))
      (node (ref "C14") (pin "2") (pinfunction "2_2") (pintype "passive"))
      (node (ref "C15") (pin "2") (pinfunction "2_2") (pintype "passive"))
      (node (ref "C18") (pin "2") (pinfunction "2_2") (pintype "passive"))
      (node (ref "C2") (pin "1") (pinfunction "1_1") (pintype "passive"))
      (node (ref "C3") (pin "1") (pinfunction "1_1") (pintype "passive"))
      (node (ref "C4") (pin "1") (pinfunction "1_1") (pintype "passive"))
      (node (ref "C5") (pin "1") (pinfunction "1_1") (pintype "passive"))
      (node (ref "C6") (pin "1") (pinfunction "1_1") (pintype "passive"))
      (node (ref "C7") (pin "1") (pinfunction "1_1") (pintype "passive"))
      (node (ref "C8") (pin "1") (pinfunction "1_1") (pintype "passive"))
      (node (ref "C9") (pin "1") (pinfunction "1_1") (pintype "passive"))
      (node (ref "D1") (pin "1") (pinfunction "1_1") (pintype "passive"))
      (node (ref "D2") (pin "1") (pinfunction "1_1") (pintype "passive"))
      (node (ref "D6") (pin "-") (pinfunction "-_-") (pintype "passive"))
      (node (ref "J1") (pin "CDN1") (pinfunction "CDN_CDN1") (pintype "bidirectional"))
      (node (ref "J1") (pin "CDN2") (pinfunction "CDN_CDN2") (pintype "bidirectional"))
      (node (ref "J1") (pin "CDN3") (pinfunction "CDN_CDN3") (pintype "bidirectional"))
      (node (ref "J1") (pin "CDN4") (pinfunction "CDN_CDN4") (pintype "bidirectional"))
      (node (ref "J1") (pin "GND1") (pinfunction "-_GND1") (pintype "bidirectional"))
      (node (ref "J1") (pin "GND2") (pinfunction "-_GND2") (pintype "bidirectional"))
      (node (ref "J1") (pin "GND3") (pinfunction "-_GND3") (pintype "bidirectional"))
      (node (ref "J1") (pin "GND4") (pinfunction "-_GND4") (pintype "bidirectional"))
      (node (ref "J2") (pin "6") (pinfunction "6_6") (pintype "bidirectional"))
      (node (ref "J2") (pin "7") (pinfunction "7_7") (pintype "bidirectional"))
      (node (ref "J4") (pin "7") (pinfunction "7_7") (pintype "bidirectional"))
      (node (ref "J6") (pin "4") (pinfunction "4_4") (pintype "bidirectional"))
      (node (ref "J7") (pin "4") (pinfunction "4_4") (pintype "bidirectional"))
      (node (ref "J8") (pin "4") (pinfunction "4_4") (pintype "bidirectional"))
      (node (ref "L1") (pin "1") (pinfunction "1_1") (pintype "passive"))
      (node (ref "Q1") (pin "1") (pinfunction "G_1") (pintype "passive"))
      (node (ref "Q3") (pin "2") (pinfunction "E_2") (pintype "passive"))
      (node (ref "Q4") (pin "2") (pinfunction "E_2") (pintype "passive"))
      (node (ref "R7") (pin "1") (pinfunction "1_1") (pintype "passive"))
      (node (ref "SW1") (pin "2") (pinfunction "2_2") (pintype "bidirectional"))
      (node (ref "U1") (pin "1") (pinfunction "GND_1") (pintype "bidirectional"))
      (node (ref "U2") (pin "1") (pinfunction "GND_1") (pintype "bidirectional"))
      (node (ref "U3") (pin "15") (pinfunction "GND_15") (pintype "bidirectional"))
      (node (ref "U4") (pin "15") (pinfunction "GND_15") (pintype "bidirectional"))
      (node (ref "U4") (pin "23") (pinfunction "GND_23") (pintype "bidirectional"))
      (node (ref "U4") (pin "35") (pinfunction "GND_35") (pintype "bidirectional"))
      (node (ref "U4") (pin "43") (pinfunction "GND_43") (pintype "bidirectional"))
      (node (ref "USB1") (pin "S1") (pinfunction "GND_S1") (pintype "bidirectional"))
      (node (ref "USB1") (pin "S2_1") (pinfunction "GND_S2_1") (pintype "bidirectional"))
      (node (ref "USB1") (pin "S2_2") (pinfunction "GND_S2_2") (pintype "bidirectional"))
      (node (ref "USB1") (pin "S2_3") (pinfunction "GND_S2_3") (pintype "bidirectional"))
      (node (ref "USB1") (pin "S3") (pinfunction "GND_S3") (pintype "bidirectional"))
      (node (ref "USB1") (pin "S4") (pinfunction "GND_S4") (pintype "bidirectional"))
      (node (ref "USB1") (pin "S5_1") (pinfunction "GND_S5_1") (pintype "bidirectional"))
      (node (ref "USB1") (pin "S5_2") (pinfunction "GND_S5_2") (pintype "bidirectional"))
      (node (ref "USB1") (pin "S5_3") (pinfunction "GND_S5_3") (pintype "bidirectional"))
      (node (ref "USB1") (pin "S6") (pinfunction "GND_S6") (pintype "bidirectional"))
    )
    (net (code "47") (name "Net-(C18-Pad1)") (class "Default")
      (node (ref "C18") (pin "1") (pinfunction "1_1") (pintype "passive"))
      (node (ref "R20") (pin "2") (pinfunction "2_2") (pintype "passive"))
    )
    (net (code "48") (name "Net-(D3-Pad+)") (class "Default")
      (node (ref "D3") (pin "+") (pinfunction "+_+") (pintype "passive"))
      (node (ref "R15") (pin "1") (pinfunction "1_1") (pintype "passive"))
    )
    (net (code "49") (name "Net-(D4-Pad-)") (class "Default")
      (node (ref "D4") (pin "-") (pinfunction "-_-") (pintype "passive"))
      (node (ref "R16") (pin "1") (pinfunction "1_1") (pintype "passive"))
    )
    (net (code "50") (name "Net-(D5-Pad-)") (class "Default")
      (node (ref "D5") (pin "-") (pinfunction "-_-") (pintype "passive"))
      (node (ref "R18") (pin "1") (pinfunction "1_1") (pintype "passive"))
    )
    (net (code "51") (name "Net-(D6-Pad+)") (class "Default")
      (node (ref "D6") (pin "+") (pinfunction "+_+") (pintype "passive"))
      (node (ref "R21") (pin "2") (pinfunction "2_2") (pintype "passive"))
    )
    (net (code "52") (name "Net-(Q1-S)") (class "Default")
      (node (ref "C1") (pin "2") (pinfunction "2_2") (pintype "passive"))
      (node (ref "C2") (pin "2") (pinfunction "2_2") (pintype "passive"))
      (node (ref "C3") (pin "2") (pinfunction "2_2") (pintype "passive"))
      (node (ref "Q1") (pin "2") (pinfunction "S_2") (pintype "passive"))
      (node (ref "U1") (pin "3") (pinfunction "IN_3") (pintype "bidirectional"))
    )
    (net (code "53") (name "Net-(Q2-G)") (class "Default")
      (node (ref "Q2") (pin "1") (pinfunction "G_1") (pintype "passive"))
      (node (ref "R3") (pin "2") (pinfunction "2_2") (pintype "passive"))
    )
    (net (code "54") (name "Net-(Q3-B)") (class "Default")
      (node (ref "Q3") (pin "1") (pinfunction "B_1") (pintype "passive"))
      (node (ref "R12") (pin "2") (pinfunction "2_2") (pintype "passive"))
    )
    (net (code "55") (name "Net-(Q4-B)") (class "Default")
      (node (ref "Q4") (pin "1") (pinfunction "B_1") (pintype "passive"))
      (node (ref "R13") (pin "2") (pinfunction "2_2") (pintype "passive"))
    )
    (net (code "56") (name "Net-(U3-GPIO0)") (class "Default")
      (node (ref "R10") (pin "1") (pinfunction "1_1") (pintype "passive"))
      (node (ref "R11") (pin "1") (pinfunction "1_1") (pintype "passive"))
      (node (ref "U3") (pin "18") (pinfunction "GPIO0_18") (pintype "bidirectional"))
    )
    (net (code "57") (name "Net-(U3-GPIO15)") (class "Default")
      (node (ref "R7") (pin "2") (pinfunction "2_2") (pintype "passive"))
      (node (ref "U3") (pin "16") (pinfunction "GPIO15_16") (pintype "bidirectional"))
    )
    (net (code "58") (name "Net-(U3-RST)") (class "Default")
      (node (ref "R5") (pin "2") (pinfunction "2_2") (pintype "passive"))
      (node (ref "U3") (pin "1") (pinfunction "RST_1") (pintype "bidirectional"))
    )
    (net (code "59") (name "Net-(U3-RXD)") (class "Default")
      (node (ref "R9") (pin "1") (pinfunction "1_1") (pintype "passive"))
      (node (ref "U3") (pin "21") (pinfunction "RXD_21") (pintype "bidirectional"))
    )
    (net (code "60") (name "Net-(U3-TXD)") (class "Default")
      (node (ref "R8") (pin "1") (pinfunction "1_1") (pintype "passive"))
      (node (ref "U3") (pin "22") (pinfunction "TXD_22") (pintype "bidirectional"))
    )
    (net (code "61") (name "Net-(U4-UCAP)") (class "Default")
      (node (ref "C16") (pin "2") (pinfunction "2_2") (pintype "passive"))
      (node (ref "U4") (pin "6") (pinfunction "UCAP_6") (pintype "bidirectional"))
    )
    (net (code "62") (name "Net-(USB1-DM)") (class "Default")
      (node (ref "D1") (pin "2") (pinfunction "2_2") (pintype "passive"))
      (node (ref "R1") (pin "1") (pinfunction "1_1") (pintype "passive"))
      (node (ref "USB1") (pin "2") (pinfunction "DM_2") (pintype "bidirectional"))
    )
    (net (code "63") (name "Net-(USB1-DP)") (class "Default")
      (node (ref "D2") (pin "2") (pinfunction "2_2") (pintype "passive"))
      (node (ref "R2") (pin "1") (pinfunction "1_1") (pintype "passive"))
      (node (ref "USB1") (pin "3") (pinfunction "DP_3") (pintype "bidirectional"))
    )
    (net (code "64") (name "Net-(USB1-VCC)") (class "Default")
      (node (ref "F1") (pin "1") (pinfunction "1_1") (pintype "bidirectional"))
      (node (ref "USB1") (pin "1") (pinfunction "VCC_1") (pintype "bidirectional"))
    )
    (net (code "65") (name "unconnected-(J2-Pad1)") (class "Default")
      (node (ref "J2") (pin "1") (pinfunction "1_1") (pintype "bidirectional"))
    )
    (net (code "66") (name "unconnected-(U3-ADC-Pad2)") (class "Default")
      (node (ref "U3") (pin "2") (pinfunction "ADC_2") (pintype "bidirectional"))
    )
    (net (code "67") (name "unconnected-(U3-CS0-Pad9)") (class "Default")
      (node (ref "U3") (pin "9") (pinfunction "CS0_9") (pintype "bidirectional"))
    )
    (net (code "68") (name "unconnected-(U3-IO9-Pad11)") (class "Default")
      (node (ref "U3") (pin "11") (pinfunction "IO9_11") (pintype "bidirectional"))
    )
    (net (code "69") (name "unconnected-(U3-IO10-Pad12)") (class "Default")
      (node (ref "U3") (pin "12") (pinfunction "IO10_12") (pintype "bidirectional"))
    )
    (net (code "70") (name "unconnected-(U3-MISO-Pad10)") (class "Default")
      (node (ref "U3") (pin "10") (pinfunction "MISO_10") (pintype "bidirectional"))
    )
    (net (code "71") (name "unconnected-(U3-MOSI-Pad13)") (class "Default")
      (node (ref "U3") (pin "13") (pinfunction "MOSI_13") (pintype "bidirectional"))
    )
    (net (code "72") (name "unconnected-(U3-SCLK-Pad14)") (class "Default")
      (node (ref "U3") (pin "14") (pinfunction "SCLK_14") (pintype "bidirectional"))
    )
    (net (code "73") (name "unconnected-(USB1-ID-Pad4)") (class "Default")
      (node (ref "USB1") (pin "4") (pinfunction "ID_4") (pintype "bidirectional"))
    )
  )
)
